# Power_Reg.net
KiCad netlist of a schematic drawn in Altium Designer
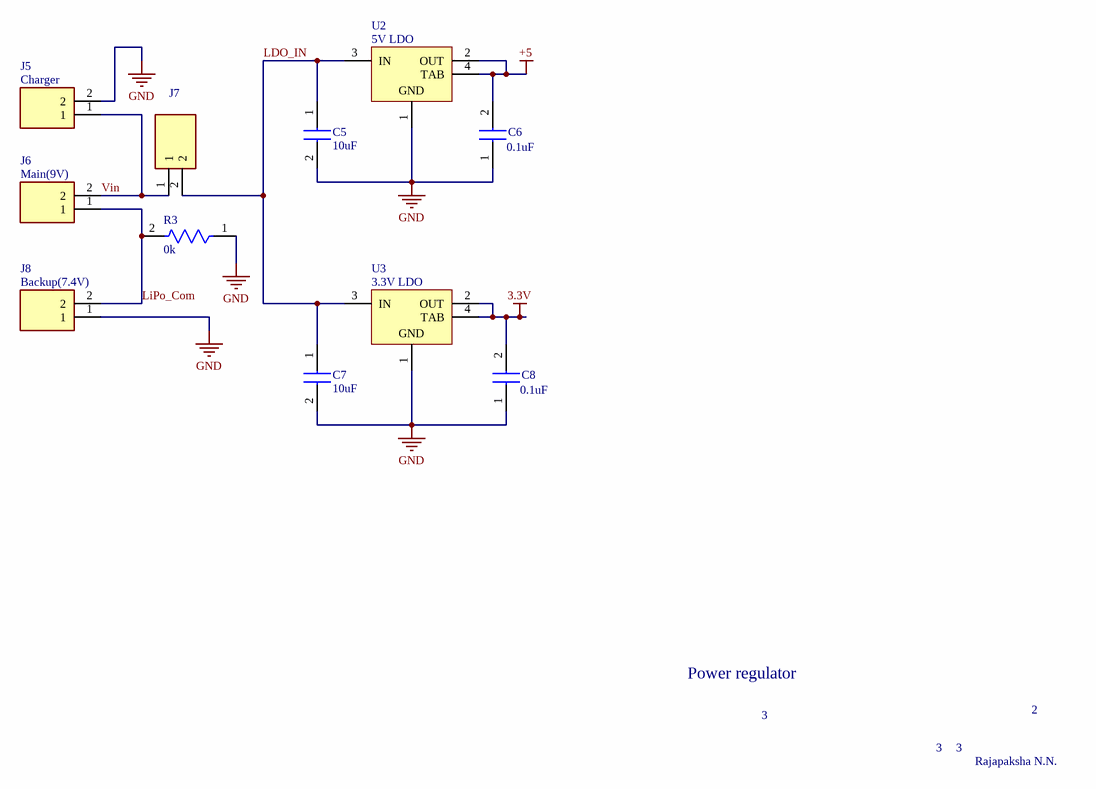
[diagram p0: Power Reg.SchDoc]

(export (version "E")
  (design (tool "Eeschema 10.0.6"))
  (components
    (comp (ref "C5")
      (value "10uF")
      (footprint "SamacSys:CAPC3216X180N")
      (description "Capacitor")
      (fields
        (field (name "MANUFACTURER_PART_NUMBER") "GRT31CR71E106KE13L")
        (field (name "MOUSER PART NUMBER") "81-GRT31CR71E106KE3L")
      )
      (libsource (lib "*") (part "GRT31CR71E106KE13L"))
    )
    (comp (ref "C6")
      (value "0.1uF")
      (footprint "SamacSys:C0805")
      (description "Capacitor")
      (fields
        (field (name "MANUFACTURER_PART_NUMBER") "C0805R104J5RACTU")
        (field (name "MOUSER PART NUMBER") "80-C0805R104J5RACTU")
      )
      (libsource (lib "*") (part "C0805R104J5RACTU"))
    )
    (comp (ref "C7")
      (value "10uF")
      (footprint "SamacSys:CAPC3216X180N")
      (description "Capacitor")
      (fields
        (field (name "MANUFACTURER_PART_NUMBER") "GRT31CR71E106KE13L")
        (field (name "MOUSER PART NUMBER") "81-GRT31CR71E106KE3L")
      )
      (libsource (lib "*") (part "GRT31CR71E106KE13L"))
    )
    (comp (ref "C8")
      (value "0.1uF")
      (footprint "SamacSys:C0805")
      (description "Capacitor")
      (fields
        (field (name "MANUFACTURER_PART_NUMBER") "C0805R104J5RACTU")
        (field (name "MOUSER PART NUMBER") "80-C0805R104J5RACTU")
      )
      (libsource (lib "*") (part "C0805R104J5RACTU"))
    )
    (comp (ref "J5")
      (value "Charger")
      (footprint "SamacSys:1727010")
      (description "Connector")
      (fields
        (field (name "MANUFACTURER_PART_NUMBER") "1727010")
        (field (name "MOUSER PART NUMBER") "651-1727010")
      )
      (libsource (lib "*") (part "1727010"))
    )
    (comp (ref "J6")
      (value "Main(9V)")
      (footprint "SamacSys:1727010")
      (description "Connector")
      (fields
        (field (name "MANUFACTURER_PART_NUMBER") "1727010")
        (field (name "MOUSER PART NUMBER") "651-1727010")
      )
      (libsource (lib "*") (part "1727010"))
    )
    (comp (ref "J7")
      (value "1727010")
      (footprint "SamacSys:1727010")
      (description "Connector")
      (fields (field (name "MOUSER PART NUMBER") "651-1727010"))
      (libsource (lib "") (part "1727010_1"))
    )
    (comp (ref "J8")
      (value "Backup(7.4V)")
      (footprint "SamacSys:1727010")
      (description "Connector")
      (fields
        (field (name "MANUFACTURER_PART_NUMBER") "1727010")
        (field (name "MOUSER PART NUMBER") "651-1727010")
      )
      (libsource (lib "*") (part "1727010"))
    )
    (comp (ref "R3")
      (value "0k")
      (footprint "FP-RK73H2A-IPC_C")
      (description "10kΩ ±1% 0.25W Chip Resistor 0805 Thick Film AEC-Q200 Qualified")
      (fields (field (name "TOLERANCE") "1%"))
      (libsource (lib "Altium Content Vault") (part "1029c3af85768c4190bb7ad29bc67b5"))
    )
    (comp (ref "U2")
      (value "5V LDO")
      (footprint "DCY0004A_L")
      (description "800mA Low-Dropout Linear Regulator, 4-pin SOT-223, Pb-Free")
      (fields
        (field (name "PARTNUMBER") "LM1117MPX-5.0/NOPB")
        (field (name "MANUFACTURER") "Texas Instruments")
      )
      (libsource (lib "Altium Content Vault") (part "PM-REG-LM1086-SOT4"))
    )
    (comp (ref "U3")
      (value "3.3V LDO")
      (footprint "DCY0004A_L")
      (description "800mA Low-Dropout Linear Regulator, 4-pin SOT-223, Pb-Free")
      (fields
        (field (name "PARTNUMBER") "LM1117MPX-3.3/NOPB")
        (field (name "MANUFACTURER") "Texas Instruments")
      )
      (libsource (lib "Altium Content Vault") (part "PM-REG-LM1086-SOT4"))
    )
  )
  (nets
    (net (code "1") (name "+5") (class "Default")
      (node (ref "C6") (pin "2") (pinfunction "2_2") (pintype "passive"))
      (node (ref "U2") (pin "2") (pinfunction "OUT_2") (pintype "power_in"))
      (node (ref "U2") (pin "4") (pinfunction "TAB_4") (pintype "power_in"))
    )
    (net (code "2") (name "/LDO_IN") (class "Default")
      (node (ref "C5") (pin "1") (pinfunction "1_1") (pintype "passive"))
      (node (ref "C7") (pin "1") (pinfunction "1_1") (pintype "passive"))
      (node (ref "J7") (pin "2") (pinfunction "2_2") (pintype "passive"))
      (node (ref "U2") (pin "3") (pinfunction "IN_3") (pintype "power_in"))
      (node (ref "U3") (pin "3") (pinfunction "IN_3") (pintype "power_in"))
    )
    (net (code "3") (name "/LiPo_Com") (class "Default")
      (node (ref "J6") (pin "1") (pinfunction "1_1") (pintype "passive"))
      (node (ref "J8") (pin "2") (pinfunction "2_2") (pintype "passive"))
      (node (ref "R3") (pin "2") (pinfunction "2_2") (pintype "passive"))
    )
    (net (code "4") (name "/Vin") (class "Default")
      (node (ref "J5") (pin "1") (pinfunction "1_1") (pintype "passive"))
      (node (ref "J6") (pin "2") (pinfunction "2_2") (pintype "passive"))
      (node (ref "J7") (pin "1") (pinfunction "1_1") (pintype "passive"))
    )
    (net (code "5") (name "3.3V") (class "Default")
      (node (ref "C8") (pin "2") (pinfunction "2_2") (pintype "passive"))
      (node (ref "U3") (pin "2") (pinfunction "OUT_2") (pintype "power_in"))
      (node (ref "U3") (pin "4") (pinfunction "TAB_4") (pintype "power_in"))
    )
    (net (code "6") (name "GND") (class "Default")
      (node (ref "C5") (pin "2") (pinfunction "2_2") (pintype "passive"))
      (node (ref "C6") (pin "1") (pinfunction "1_1") (pintype "passive"))
      (node (ref "C7") (pin "2") (pinfunction "2_2") (pintype "passive"))
      (node (ref "C8") (pin "1") (pinfunction "1_1") (pintype "passive"))
      (node (ref "J5") (pin "2") (pinfunction "2_2") (pintype "passive"))
      (node (ref "J8") (pin "1") (pinfunction "1_1") (pintype "passive"))
      (node (ref "R3") (pin "1") (pinfunction "1_1") (pintype "passive"))
      (node (ref "U2") (pin "1") (pinfunction "GND_1") (pintype "power_in"))
      (node (ref "U3") (pin "1") (pinfunction "GND_1") (pintype "power_in"))
    )
  )
)
